# arduino-double.net
KiCad netlist of a schematic drawn in EAGLE
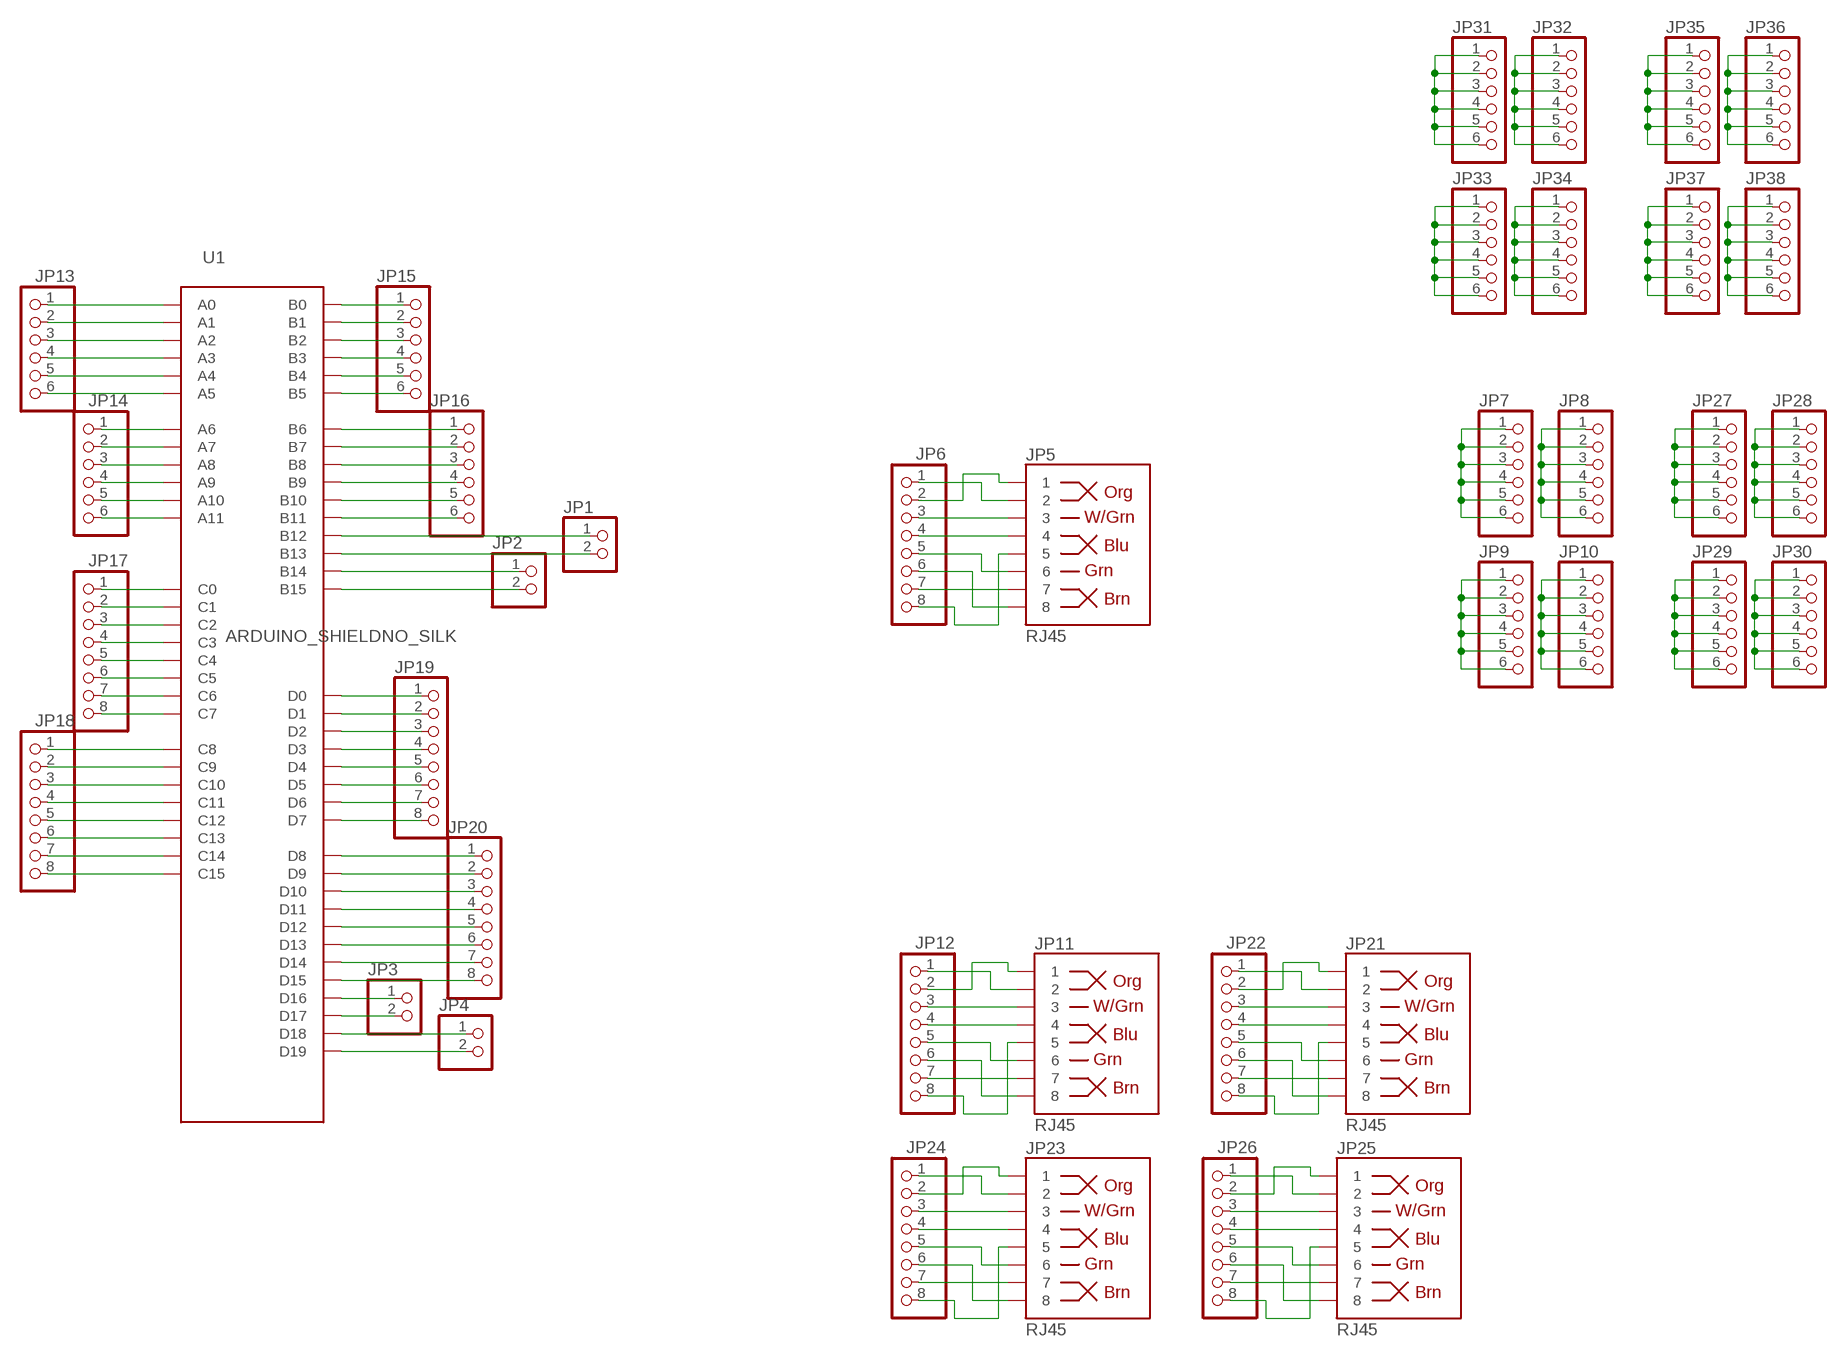
[diagram p0: schematic, sheet 1]

(export (version "E")
  (design (tool "Eeschema 10.0.6"))
  (components
    (comp (ref "JP1")
      (value "PINHD-1X2")
      (footprint "eagle-import:1X02")
      (libsource (lib "eagle-import") (part "PINHD-1X2"))
    )
    (comp (ref "JP2")
      (value "PINHD-1X2")
      (footprint "eagle-import:1X02")
      (libsource (lib "eagle-import") (part "PINHD-1X2"))
    )
    (comp (ref "JP3")
      (value "PINHD-1X2")
      (footprint "eagle-import:1X02")
      (libsource (lib "eagle-import") (part "PINHD-1X2"))
    )
    (comp (ref "JP4")
      (value "PINHD-1X2")
      (footprint "eagle-import:1X02")
      (libsource (lib "eagle-import") (part "PINHD-1X2"))
    )
    (comp (ref "JP5")
      (value "RJ45")
      (footprint "eagle-import:RJ45-8")
      (libsource (lib "eagle-import") (part "RJ45-8PTH"))
    )
    (comp (ref "JP6")
      (value "PINHD-1X8")
      (footprint "eagle-import:1X08")
      (libsource (lib "eagle-import") (part "PINHD-1X8"))
    )
    (comp (ref "JP7")
      (value "PINHD-1X6")
      (footprint "eagle-import:1X06")
      (libsource (lib "eagle-import") (part "PINHD-1X6"))
    )
    (comp (ref "JP8")
      (value "PINHD-1X6")
      (footprint "eagle-import:1X06")
      (libsource (lib "eagle-import") (part "PINHD-1X6"))
    )
    (comp (ref "JP9")
      (value "PINHD-1X6")
      (footprint "eagle-import:1X06")
      (libsource (lib "eagle-import") (part "PINHD-1X6"))
    )
    (comp (ref "JP10")
      (value "PINHD-1X6")
      (footprint "eagle-import:1X06")
      (libsource (lib "eagle-import") (part "PINHD-1X6"))
    )
    (comp (ref "JP11")
      (value "RJ45")
      (footprint "eagle-import:RJ45-8")
      (libsource (lib "eagle-import") (part "RJ45-8PTH"))
    )
    (comp (ref "JP12")
      (value "PINHD-1X8")
      (footprint "eagle-import:1X08")
      (libsource (lib "eagle-import") (part "PINHD-1X8"))
    )
    (comp (ref "JP13")
      (value "PINHD-1X6")
      (footprint "eagle-import:1X06")
      (libsource (lib "eagle-import") (part "PINHD-1X6"))
    )
    (comp (ref "JP14")
      (value "PINHD-1X6")
      (footprint "eagle-import:1X06")
      (libsource (lib "eagle-import") (part "PINHD-1X6"))
    )
    (comp (ref "JP15")
      (value "PINHD-1X6")
      (footprint "eagle-import:1X06")
      (libsource (lib "eagle-import") (part "PINHD-1X6"))
    )
    (comp (ref "JP16")
      (value "PINHD-1X6")
      (footprint "eagle-import:1X06")
      (libsource (lib "eagle-import") (part "PINHD-1X6"))
    )
    (comp (ref "JP17")
      (value "PINHD-1X8")
      (footprint "eagle-import:1X08")
      (libsource (lib "eagle-import") (part "PINHD-1X8"))
    )
    (comp (ref "JP18")
      (value "PINHD-1X8")
      (footprint "eagle-import:1X08")
      (libsource (lib "eagle-import") (part "PINHD-1X8"))
    )
    (comp (ref "JP19")
      (value "PINHD-1X8")
      (footprint "eagle-import:1X08")
      (libsource (lib "eagle-import") (part "PINHD-1X8"))
    )
    (comp (ref "JP20")
      (value "PINHD-1X8")
      (footprint "eagle-import:1X08")
      (libsource (lib "eagle-import") (part "PINHD-1X8"))
    )
    (comp (ref "JP21")
      (value "RJ45")
      (footprint "eagle-import:RJ45-8")
      (libsource (lib "eagle-import") (part "RJ45-8PTH"))
    )
    (comp (ref "JP22")
      (value "PINHD-1X8")
      (footprint "eagle-import:1X08")
      (libsource (lib "eagle-import") (part "PINHD-1X8"))
    )
    (comp (ref "JP23")
      (value "RJ45")
      (footprint "eagle-import:RJ45-8")
      (libsource (lib "eagle-import") (part "RJ45-8PTH"))
    )
    (comp (ref "JP24")
      (value "PINHD-1X8")
      (footprint "eagle-import:1X08")
      (libsource (lib "eagle-import") (part "PINHD-1X8"))
    )
    (comp (ref "JP25")
      (value "RJ45")
      (footprint "eagle-import:RJ45-8")
      (libsource (lib "eagle-import") (part "RJ45-8PTH"))
    )
    (comp (ref "JP26")
      (value "PINHD-1X8")
      (footprint "eagle-import:1X08")
      (libsource (lib "eagle-import") (part "PINHD-1X8"))
    )
    (comp (ref "JP27")
      (value "PINHD-1X6")
      (footprint "eagle-import:1X06")
      (libsource (lib "eagle-import") (part "PINHD-1X6"))
    )
    (comp (ref "JP28")
      (value "PINHD-1X6")
      (footprint "eagle-import:1X06")
      (libsource (lib "eagle-import") (part "PINHD-1X6"))
    )
    (comp (ref "JP29")
      (value "PINHD-1X6")
      (footprint "eagle-import:1X06")
      (libsource (lib "eagle-import") (part "PINHD-1X6"))
    )
    (comp (ref "JP30")
      (value "PINHD-1X6")
      (footprint "eagle-import:1X06")
      (libsource (lib "eagle-import") (part "PINHD-1X6"))
    )
    (comp (ref "JP31")
      (value "PINHD-1X6")
      (footprint "eagle-import:1X06")
      (libsource (lib "eagle-import") (part "PINHD-1X6"))
    )
    (comp (ref "JP32")
      (value "PINHD-1X6")
      (footprint "eagle-import:1X06")
      (libsource (lib "eagle-import") (part "PINHD-1X6"))
    )
    (comp (ref "JP33")
      (value "PINHD-1X6")
      (footprint "eagle-import:1X06")
      (libsource (lib "eagle-import") (part "PINHD-1X6"))
    )
    (comp (ref "JP34")
      (value "PINHD-1X6")
      (footprint "eagle-import:1X06")
      (libsource (lib "eagle-import") (part "PINHD-1X6"))
    )
    (comp (ref "JP35")
      (value "PINHD-1X6")
      (footprint "eagle-import:1X06")
      (libsource (lib "eagle-import") (part "PINHD-1X6"))
    )
    (comp (ref "JP36")
      (value "PINHD-1X6")
      (footprint "eagle-import:1X06")
      (libsource (lib "eagle-import") (part "PINHD-1X6"))
    )
    (comp (ref "JP37")
      (value "PINHD-1X6")
      (footprint "eagle-import:1X06")
      (libsource (lib "eagle-import") (part "PINHD-1X6"))
    )
    (comp (ref "JP38")
      (value "PINHD-1X6")
      (footprint "eagle-import:1X06")
      (libsource (lib "eagle-import") (part "PINHD-1X6"))
    )
    (comp (ref "U1")
      (value "ARDUINO_SHIELDNO_SILK")
      (footprint "eagle-import:DUEMILANOVE_VIAS")
      (libsource (lib "eagle-import") (part "ARDUINO_SHIELDNO_SILK"))
    )
  )
  (nets
    (net (code "1") (name "Net-(JP1-Pad1)") (class "Default")
      (node (ref "JP1") (pin "1") (pinfunction "1_1") (pintype "passive"))
      (node (ref "U1") (pin "B12") (pinfunction "B12_B12") (pintype "bidirectional"))
    )
    (net (code "2") (name "Net-(JP1-Pad2)") (class "Default")
      (node (ref "JP1") (pin "2") (pinfunction "2_2") (pintype "passive"))
      (node (ref "U1") (pin "B13") (pinfunction "B13_B13") (pintype "bidirectional"))
    )
    (net (code "3") (name "Net-(JP2-Pad1)") (class "Default")
      (node (ref "JP2") (pin "1") (pinfunction "1_1") (pintype "passive"))
      (node (ref "U1") (pin "B14") (pinfunction "B14_B14") (pintype "bidirectional"))
    )
    (net (code "4") (name "Net-(JP2-Pad2)") (class "Default")
      (node (ref "JP2") (pin "2") (pinfunction "2_2") (pintype "passive"))
      (node (ref "U1") (pin "B15") (pinfunction "B15_B15") (pintype "bidirectional"))
    )
    (net (code "5") (name "Net-(JP3-Pad1)") (class "Default")
      (node (ref "JP3") (pin "1") (pinfunction "1_1") (pintype "passive"))
      (node (ref "U1") (pin "D16") (pinfunction "D16_D16") (pintype "bidirectional"))
    )
    (net (code "6") (name "Net-(JP3-Pad2)") (class "Default")
      (node (ref "JP3") (pin "2") (pinfunction "2_2") (pintype "passive"))
      (node (ref "U1") (pin "D17") (pinfunction "D17_D17") (pintype "bidirectional"))
    )
    (net (code "7") (name "Net-(JP4-Pad1)") (class "Default")
      (node (ref "JP4") (pin "1") (pinfunction "1_1") (pintype "passive"))
      (node (ref "U1") (pin "D18") (pinfunction "D18_D18") (pintype "bidirectional"))
    )
    (net (code "8") (name "Net-(JP4-Pad2)") (class "Default")
      (node (ref "JP4") (pin "2") (pinfunction "2_2") (pintype "passive"))
      (node (ref "U1") (pin "D19") (pinfunction "D19_D19") (pintype "bidirectional"))
    )
    (net (code "9") (name "Net-(JP5-Pad1)") (class "Default")
      (node (ref "JP5") (pin "1") (pinfunction "1_1") (pintype "bidirectional"))
      (node (ref "JP6") (pin "2") (pinfunction "2_2") (pintype "passive"))
    )
    (net (code "10") (name "Net-(JP5-Pad2)") (class "Default")
      (node (ref "JP5") (pin "2") (pinfunction "2_2") (pintype "bidirectional"))
      (node (ref "JP6") (pin "1") (pinfunction "1_1") (pintype "passive"))
    )
    (net (code "11") (name "Net-(JP5-Pad3)") (class "Default")
      (node (ref "JP5") (pin "3") (pinfunction "3_3") (pintype "bidirectional"))
      (node (ref "JP6") (pin "3") (pinfunction "3_3") (pintype "passive"))
    )
    (net (code "12") (name "Net-(JP5-Pad4)") (class "Default")
      (node (ref "JP5") (pin "4") (pinfunction "4_4") (pintype "bidirectional"))
      (node (ref "JP6") (pin "4") (pinfunction "4_4") (pintype "passive"))
    )
    (net (code "13") (name "Net-(JP5-Pad5)") (class "Default")
      (node (ref "JP5") (pin "5") (pinfunction "5_5") (pintype "bidirectional"))
      (node (ref "JP6") (pin "8") (pinfunction "8_8") (pintype "passive"))
    )
    (net (code "14") (name "Net-(JP5-Pad6)") (class "Default")
      (node (ref "JP5") (pin "6") (pinfunction "6_6") (pintype "bidirectional"))
      (node (ref "JP6") (pin "5") (pinfunction "5_5") (pintype "passive"))
    )
    (net (code "15") (name "Net-(JP5-Pad7)") (class "Default")
      (node (ref "JP5") (pin "7") (pinfunction "7_7") (pintype "bidirectional"))
      (node (ref "JP6") (pin "7") (pinfunction "7_7") (pintype "passive"))
    )
    (net (code "16") (name "Net-(JP5-Pad8)") (class "Default")
      (node (ref "JP5") (pin "8") (pinfunction "8_8") (pintype "bidirectional"))
      (node (ref "JP6") (pin "6") (pinfunction "6_6") (pintype "passive"))
    )
    (net (code "17") (name "Net-(JP7-Pad1)") (class "Default")
      (node (ref "JP7") (pin "1") (pinfunction "1_1") (pintype "passive"))
      (node (ref "JP7") (pin "2") (pinfunction "2_2") (pintype "passive"))
      (node (ref "JP7") (pin "3") (pinfunction "3_3") (pintype "passive"))
      (node (ref "JP7") (pin "4") (pinfunction "4_4") (pintype "passive"))
      (node (ref "JP7") (pin "5") (pinfunction "5_5") (pintype "passive"))
      (node (ref "JP7") (pin "6") (pinfunction "6_6") (pintype "passive"))
    )
    (net (code "18") (name "Net-(JP8-Pad1)") (class "Default")
      (node (ref "JP8") (pin "1") (pinfunction "1_1") (pintype "passive"))
      (node (ref "JP8") (pin "2") (pinfunction "2_2") (pintype "passive"))
      (node (ref "JP8") (pin "3") (pinfunction "3_3") (pintype "passive"))
      (node (ref "JP8") (pin "4") (pinfunction "4_4") (pintype "passive"))
      (node (ref "JP8") (pin "5") (pinfunction "5_5") (pintype "passive"))
      (node (ref "JP8") (pin "6") (pinfunction "6_6") (pintype "passive"))
    )
    (net (code "19") (name "Net-(JP9-Pad1)") (class "Default")
      (node (ref "JP9") (pin "1") (pinfunction "1_1") (pintype "passive"))
      (node (ref "JP9") (pin "2") (pinfunction "2_2") (pintype "passive"))
      (node (ref "JP9") (pin "3") (pinfunction "3_3") (pintype "passive"))
      (node (ref "JP9") (pin "4") (pinfunction "4_4") (pintype "passive"))
      (node (ref "JP9") (pin "5") (pinfunction "5_5") (pintype "passive"))
      (node (ref "JP9") (pin "6") (pinfunction "6_6") (pintype "passive"))
    )
    (net (code "20") (name "Net-(JP10-Pad1)") (class "Default")
      (node (ref "JP10") (pin "1") (pinfunction "1_1") (pintype "passive"))
      (node (ref "JP10") (pin "2") (pinfunction "2_2") (pintype "passive"))
      (node (ref "JP10") (pin "3") (pinfunction "3_3") (pintype "passive"))
      (node (ref "JP10") (pin "4") (pinfunction "4_4") (pintype "passive"))
      (node (ref "JP10") (pin "5") (pinfunction "5_5") (pintype "passive"))
      (node (ref "JP10") (pin "6") (pinfunction "6_6") (pintype "passive"))
    )
    (net (code "21") (name "Net-(JP11-Pad1)") (class "Default")
      (node (ref "JP11") (pin "1") (pinfunction "1_1") (pintype "bidirectional"))
      (node (ref "JP12") (pin "2") (pinfunction "2_2") (pintype "passive"))
    )
    (net (code "22") (name "Net-(JP11-Pad2)") (class "Default")
      (node (ref "JP11") (pin "2") (pinfunction "2_2") (pintype "bidirectional"))
      (node (ref "JP12") (pin "1") (pinfunction "1_1") (pintype "passive"))
    )
    (net (code "23") (name "Net-(JP11-Pad3)") (class "Default")
      (node (ref "JP11") (pin "3") (pinfunction "3_3") (pintype "bidirectional"))
      (node (ref "JP12") (pin "3") (pinfunction "3_3") (pintype "passive"))
    )
    (net (code "24") (name "Net-(JP11-Pad4)") (class "Default")
      (node (ref "JP11") (pin "4") (pinfunction "4_4") (pintype "bidirectional"))
      (node (ref "JP12") (pin "4") (pinfunction "4_4") (pintype "passive"))
    )
    (net (code "25") (name "Net-(JP11-Pad5)") (class "Default")
      (node (ref "JP11") (pin "5") (pinfunction "5_5") (pintype "bidirectional"))
      (node (ref "JP12") (pin "8") (pinfunction "8_8") (pintype "passive"))
    )
    (net (code "26") (name "Net-(JP11-Pad6)") (class "Default")
      (node (ref "JP11") (pin "6") (pinfunction "6_6") (pintype "bidirectional"))
      (node (ref "JP12") (pin "5") (pinfunction "5_5") (pintype "passive"))
    )
    (net (code "27") (name "Net-(JP11-Pad7)") (class "Default")
      (node (ref "JP11") (pin "7") (pinfunction "7_7") (pintype "bidirectional"))
      (node (ref "JP12") (pin "7") (pinfunction "7_7") (pintype "passive"))
    )
    (net (code "28") (name "Net-(JP11-Pad8)") (class "Default")
      (node (ref "JP11") (pin "8") (pinfunction "8_8") (pintype "bidirectional"))
      (node (ref "JP12") (pin "6") (pinfunction "6_6") (pintype "passive"))
    )
    (net (code "29") (name "Net-(JP13-Pad1)") (class "Default")
      (node (ref "JP13") (pin "1") (pinfunction "1_1") (pintype "passive"))
      (node (ref "U1") (pin "A0") (pinfunction "A0_A0") (pintype "bidirectional"))
    )
    (net (code "30") (name "Net-(JP13-Pad2)") (class "Default")
      (node (ref "JP13") (pin "2") (pinfunction "2_2") (pintype "passive"))
      (node (ref "U1") (pin "A1") (pinfunction "A1_A1") (pintype "bidirectional"))
    )
    (net (code "31") (name "Net-(JP13-Pad3)") (class "Default")
      (node (ref "JP13") (pin "3") (pinfunction "3_3") (pintype "passive"))
      (node (ref "U1") (pin "A2") (pinfunction "A2_A2") (pintype "bidirectional"))
    )
    (net (code "32") (name "Net-(JP13-Pad4)") (class "Default")
      (node (ref "JP13") (pin "4") (pinfunction "4_4") (pintype "passive"))
      (node (ref "U1") (pin "A3") (pinfunction "A3_A3") (pintype "bidirectional"))
    )
    (net (code "33") (name "Net-(JP13-Pad5)") (class "Default")
      (node (ref "JP13") (pin "5") (pinfunction "5_5") (pintype "passive"))
      (node (ref "U1") (pin "A4") (pinfunction "A4_A4") (pintype "bidirectional"))
    )
    (net (code "34") (name "Net-(JP13-Pad6)") (class "Default")
      (node (ref "JP13") (pin "6") (pinfunction "6_6") (pintype "passive"))
      (node (ref "U1") (pin "A5") (pinfunction "A5_A5") (pintype "bidirectional"))
    )
    (net (code "35") (name "Net-(JP14-Pad1)") (class "Default")
      (node (ref "JP14") (pin "1") (pinfunction "1_1") (pintype "passive"))
      (node (ref "U1") (pin "A6") (pinfunction "A6_A6") (pintype "bidirectional"))
    )
    (net (code "36") (name "Net-(JP14-Pad2)") (class "Default")
      (node (ref "JP14") (pin "2") (pinfunction "2_2") (pintype "passive"))
      (node (ref "U1") (pin "A7") (pinfunction "A7_A7") (pintype "bidirectional"))
    )
    (net (code "37") (name "Net-(JP14-Pad3)") (class "Default")
      (node (ref "JP14") (pin "3") (pinfunction "3_3") (pintype "passive"))
      (node (ref "U1") (pin "A8") (pinfunction "A8_A8") (pintype "bidirectional"))
    )
    (net (code "38") (name "Net-(JP14-Pad4)") (class "Default")
      (node (ref "JP14") (pin "4") (pinfunction "4_4") (pintype "passive"))
      (node (ref "U1") (pin "A9") (pinfunction "A9_A9") (pintype "bidirectional"))
    )
    (net (code "39") (name "Net-(JP14-Pad5)") (class "Default")
      (node (ref "JP14") (pin "5") (pinfunction "5_5") (pintype "passive"))
      (node (ref "U1") (pin "A10") (pinfunction "A10_A10") (pintype "bidirectional"))
    )
    (net (code "40") (name "Net-(JP14-Pad6)") (class "Default")
      (node (ref "JP14") (pin "6") (pinfunction "6_6") (pintype "passive"))
      (node (ref "U1") (pin "A11") (pinfunction "A11_A11") (pintype "bidirectional"))
    )
    (net (code "41") (name "Net-(JP15-Pad1)") (class "Default")
      (node (ref "JP15") (pin "1") (pinfunction "1_1") (pintype "passive"))
      (node (ref "U1") (pin "B0") (pinfunction "B0_B0") (pintype "bidirectional"))
    )
    (net (code "42") (name "Net-(JP15-Pad2)") (class "Default")
      (node (ref "JP15") (pin "2") (pinfunction "2_2") (pintype "passive"))
      (node (ref "U1") (pin "B1") (pinfunction "B1_B1") (pintype "bidirectional"))
    )
    (net (code "43") (name "Net-(JP15-Pad3)") (class "Default")
      (node (ref "JP15") (pin "3") (pinfunction "3_3") (pintype "passive"))
      (node (ref "U1") (pin "B2") (pinfunction "B2_B2") (pintype "bidirectional"))
    )
    (net (code "44") (name "Net-(JP15-Pad4)") (class "Default")
      (node (ref "JP15") (pin "4") (pinfunction "4_4") (pintype "passive"))
      (node (ref "U1") (pin "B3") (pinfunction "B3_B3") (pintype "bidirectional"))
    )
    (net (code "45") (name "Net-(JP15-Pad5)") (class "Default")
      (node (ref "JP15") (pin "5") (pinfunction "5_5") (pintype "passive"))
      (node (ref "U1") (pin "B4") (pinfunction "B4_B4") (pintype "bidirectional"))
    )
    (net (code "46") (name "Net-(JP15-Pad6)") (class "Default")
      (node (ref "JP15") (pin "6") (pinfunction "6_6") (pintype "passive"))
      (node (ref "U1") (pin "B5") (pinfunction "B5_B5") (pintype "bidirectional"))
    )
    (net (code "47") (name "Net-(JP16-Pad1)") (class "Default")
      (node (ref "JP16") (pin "1") (pinfunction "1_1") (pintype "passive"))
      (node (ref "U1") (pin "B6") (pinfunction "B6_B6") (pintype "bidirectional"))
    )
    (net (code "48") (name "Net-(JP16-Pad2)") (class "Default")
      (node (ref "JP16") (pin "2") (pinfunction "2_2") (pintype "passive"))
      (node (ref "U1") (pin "B7") (pinfunction "B7_B7") (pintype "bidirectional"))
    )
    (net (code "49") (name "Net-(JP16-Pad3)") (class "Default")
      (node (ref "JP16") (pin "3") (pinfunction "3_3") (pintype "passive"))
      (node (ref "U1") (pin "B8") (pinfunction "B8_B8") (pintype "bidirectional"))
    )
    (net (code "50") (name "Net-(JP16-Pad4)") (class "Default")
      (node (ref "JP16") (pin "4") (pinfunction "4_4") (pintype "passive"))
      (node (ref "U1") (pin "B9") (pinfunction "B9_B9") (pintype "bidirectional"))
    )
    (net (code "51") (name "Net-(JP16-Pad5)") (class "Default")
      (node (ref "JP16") (pin "5") (pinfunction "5_5") (pintype "passive"))
      (node (ref "U1") (pin "B10") (pinfunction "B10_B10") (pintype "bidirectional"))
    )
    (net (code "52") (name "Net-(JP16-Pad6)") (class "Default")
      (node (ref "JP16") (pin "6") (pinfunction "6_6") (pintype "passive"))
      (node (ref "U1") (pin "B11") (pinfunction "B11_B11") (pintype "bidirectional"))
    )
    (net (code "53") (name "Net-(JP17-Pad1)") (class "Default")
      (node (ref "JP17") (pin "1") (pinfunction "1_1") (pintype "passive"))
      (node (ref "U1") (pin "C0") (pinfunction "C0_C0") (pintype "bidirectional"))
    )
    (net (code "54") (name "Net-(JP17-Pad2)") (class "Default")
      (node (ref "JP17") (pin "2") (pinfunction "2_2") (pintype "passive"))
      (node (ref "U1") (pin "C1") (pinfunction "C1_C1") (pintype "bidirectional"))
    )
    (net (code "55") (name "Net-(JP17-Pad3)") (class "Default")
      (node (ref "JP17") (pin "3") (pinfunction "3_3") (pintype "passive"))
      (node (ref "U1") (pin "C2") (pinfunction "C2_C2") (pintype "bidirectional"))
    )
    (net (code "56") (name "Net-(JP17-Pad4)") (class "Default")
      (node (ref "JP17") (pin "4") (pinfunction "4_4") (pintype "passive"))
      (node (ref "U1") (pin "C3") (pinfunction "C3_C3") (pintype "bidirectional"))
    )
    (net (code "57") (name "Net-(JP17-Pad5)") (class "Default")
      (node (ref "JP17") (pin "5") (pinfunction "5_5") (pintype "passive"))
      (node (ref "U1") (pin "C4") (pinfunction "C4_C4") (pintype "bidirectional"))
    )
    (net (code "58") (name "Net-(JP17-Pad6)") (class "Default")
      (node (ref "JP17") (pin "6") (pinfunction "6_6") (pintype "passive"))
      (node (ref "U1") (pin "C5") (pinfunction "C5_C5") (pintype "bidirectional"))
    )
    (net (code "59") (name "Net-(JP17-Pad7)") (class "Default")
      (node (ref "JP17") (pin "7") (pinfunction "7_7") (pintype "passive"))
      (node (ref "U1") (pin "C6") (pinfunction "C6_C6") (pintype "bidirectional"))
    )
    (net (code "60") (name "Net-(JP17-Pad8)") (class "Default")
      (node (ref "JP17") (pin "8") (pinfunction "8_8") (pintype "passive"))
      (node (ref "U1") (pin "C7") (pinfunction "C7_C7") (pintype "bidirectional"))
    )
    (net (code "61") (name "Net-(JP18-Pad1)") (class "Default")
      (node (ref "JP18") (pin "1") (pinfunction "1_1") (pintype "passive"))
      (node (ref "U1") (pin "C8") (pinfunction "C8_C8") (pintype "bidirectional"))
    )
    (net (code "62") (name "Net-(JP18-Pad2)") (class "Default")
      (node (ref "JP18") (pin "2") (pinfunction "2_2") (pintype "passive"))
      (node (ref "U1") (pin "C9") (pinfunction "C9_C9") (pintype "bidirectional"))
    )
    (net (code "63") (name "Net-(JP18-Pad3)") (class "Default")
      (node (ref "JP18") (pin "3") (pinfunction "3_3") (pintype "passive"))
      (node (ref "U1") (pin "C10") (pinfunction "C10_C10") (pintype "bidirectional"))
    )
    (net (code "64") (name "Net-(JP18-Pad4)") (class "Default")
      (node (ref "JP18") (pin "4") (pinfunction "4_4") (pintype "passive"))
      (node (ref "U1") (pin "C11") (pinfunction "C11_C11") (pintype "bidirectional"))
    )
    (net (code "65") (name "Net-(JP18-Pad5)") (class "Default")
      (node (ref "JP18") (pin "5") (pinfunction "5_5") (pintype "passive"))
      (node (ref "U1") (pin "C12") (pinfunction "C12_C12") (pintype "bidirectional"))
    )
    (net (code "66") (name "Net-(JP18-Pad6)") (class "Default")
      (node (ref "JP18") (pin "6") (pinfunction "6_6") (pintype "passive"))
      (node (ref "U1") (pin "C13") (pinfunction "C13_C13") (pintype "bidirectional"))
    )
    (net (code "67") (name "Net-(JP18-Pad7)") (class "Default")
      (node (ref "JP18") (pin "7") (pinfunction "7_7") (pintype "passive"))
      (node (ref "U1") (pin "C14") (pinfunction "C14_C14") (pintype "bidirectional"))
    )
    (net (code "68") (name "Net-(JP18-Pad8)") (class "Default")
      (node (ref "JP18") (pin "8") (pinfunction "8_8") (pintype "passive"))
      (node (ref "U1") (pin "C15") (pinfunction "C15_C15") (pintype "bidirectional"))
    )
    (net (code "69") (name "Net-(JP19-Pad1)") (class "Default")
      (node (ref "JP19") (pin "1") (pinfunction "1_1") (pintype "passive"))
      (node (ref "U1") (pin "D0") (pinfunction "D0_D0") (pintype "bidirectional"))
    )
    (net (code "70") (name "Net-(JP19-Pad2)") (class "Default")
      (node (ref "JP19") (pin "2") (pinfunction "2_2") (pintype "passive"))
      (node (ref "U1") (pin "D1") (pinfunction "D1_D1") (pintype "bidirectional"))
    )
    (net (code "71") (name "Net-(JP19-Pad3)") (class "Default")
      (node (ref "JP19") (pin "3") (pinfunction "3_3") (pintype "passive"))
      (node (ref "U1") (pin "D2") (pinfunction "D2_D2") (pintype "bidirectional"))
    )
    (net (code "72") (name "Net-(JP19-Pad4)") (class "Default")
      (node (ref "JP19") (pin "4") (pinfunction "4_4") (pintype "passive"))
      (node (ref "U1") (pin "D3") (pinfunction "D3_D3") (pintype "bidirectional"))
    )
    (net (code "73") (name "Net-(JP19-Pad5)") (class "Default")
      (node (ref "JP19") (pin "5") (pinfunction "5_5") (pintype "passive"))
      (node (ref "U1") (pin "D4") (pinfunction "D4_D4") (pintype "bidirectional"))
    )
    (net (code "74") (name "Net-(JP19-Pad6)") (class "Default")
      (node (ref "JP19") (pin "6") (pinfunction "6_6") (pintype "passive"))
      (node (ref "U1") (pin "D5") (pinfunction "D5_D5") (pintype "bidirectional"))
    )
    (net (code "75") (name "Net-(JP19-Pad7)") (class "Default")
      (node (ref "JP19") (pin "7") (pinfunction "7_7") (pintype "passive"))
      (node (ref "U1") (pin "D6") (pinfunction "D6_D6") (pintype "bidirectional"))
    )
    (net (code "76") (name "Net-(JP19-Pad8)") (class "Default")
      (node (ref "JP19") (pin "8") (pinfunction "8_8") (pintype "passive"))
      (node (ref "U1") (pin "D7") (pinfunction "D7_D7") (pintype "bidirectional"))
    )
    (net (code "77") (name "Net-(JP20-Pad1)") (class "Default")
      (node (ref "JP20") (pin "1") (pinfunction "1_1") (pintype "passive"))
      (node (ref "U1") (pin "D8") (pinfunction "D8_D8") (pintype "bidirectional"))
    )
    (net (code "78") (name "Net-(JP20-Pad2)") (class "Default")
      (node (ref "JP20") (pin "2") (pinfunction "2_2") (pintype "passive"))
      (node (ref "U1") (pin "D9") (pinfunction "D9_D9") (pintype "bidirectional"))
    )
    (net (code "79") (name "Net-(JP20-Pad3)") (class "Default")
      (node (ref "JP20") (pin "3") (pinfunction "3_3") (pintype "passive"))
      (node (ref "U1") (pin "D10") (pinfunction "D10_D10") (pintype "bidirectional"))
    )
    (net (code "80") (name "Net-(JP20-Pad4)") (class "Default")
      (node (ref "JP20") (pin "4") (pinfunction "4_4") (pintype "passive"))
      (node (ref "U1") (pin "D11") (pinfunction "D11_D11") (pintype "bidirectional"))
    )
    (net (code "81") (name "Net-(JP20-Pad5)") (class "Default")
      (node (ref "JP20") (pin "5") (pinfunction "5_5") (pintype "passive"))
      (node (ref "U1") (pin "D12") (pinfunction "D12_D12") (pintype "bidirectional"))
    )
    (net (code "82") (name "Net-(JP20-Pad6)") (class "Default")
      (node (ref "JP20") (pin "6") (pinfunction "6_6") (pintype "passive"))
      (node (ref "U1") (pin "D13") (pinfunction "D13_D13") (pintype "bidirectional"))
    )
    (net (code "83") (name "Net-(JP20-Pad7)") (class "Default")
      (node (ref "JP20") (pin "7") (pinfunction "7_7") (pintype "passive"))
      (node (ref "U1") (pin "D14") (pinfunction "D14_D14") (pintype "bidirectional"))
    )
    (net (code "84") (name "Net-(JP20-Pad8)") (class "Default")
      (node (ref "JP20") (pin "8") (pinfunction "8_8") (pintype "passive"))
      (node (ref "U1") (pin "D15") (pinfunction "D15_D15") (pintype "bidirectional"))
    )
    (net (code "85") (name "Net-(JP21-Pad1)") (class "Default")
      (node (ref "JP21") (pin "1") (pinfunction "1_1") (pintype "bidirectional"))
      (node (ref "JP22") (pin "2") (pinfunction "2_2") (pintype "passive"))
    )
    (net (code "86") (name "Net-(JP21-Pad2)") (class "Default")
      (node (ref "JP21") (pin "2") (pinfunction "2_2") (pintype "bidirectional"))
      (node (ref "JP22") (pin "1") (pinfunction "1_1") (pintype "passive"))
    )
    (net (code "87") (name "Net-(JP21-Pad3)") (class "Default")
      (node (ref "JP21") (pin "3") (pinfunction "3_3") (pintype "bidirectional"))
      (node (ref "JP22") (pin "3") (pinfunction "3_3") (pintype "passive"))
    )
    (net (code "88") (name "Net-(JP21-Pad4)") (class "Default")
      (node (ref "JP21") (pin "4") (pinfunction "4_4") (pintype "bidirectional"))
      (node (ref "JP22") (pin "4") (pinfunction "4_4") (pintype "passive"))
    )
    (net (code "89") (name "Net-(JP21-Pad5)") (class "Default")
      (node (ref "JP21") (pin "5") (pinfunction "5_5") (pintype "bidirectional"))
      (node (ref "JP22") (pin "8") (pinfunction "8_8") (pintype "passive"))
    )
    (net (code "90") (name "Net-(JP21-Pad6)") (class "Default")
      (node (ref "JP21") (pin "6") (pinfunction "6_6") (pintype "bidirectional"))
      (node (ref "JP22") (pin "5") (pinfunction "5_5") (pintype "passive"))
    )
    (net (code "91") (name "Net-(JP21-Pad7)") (class "Default")
      (node (ref "JP21") (pin "7") (pinfunction "7_7") (pintype "bidirectional"))
      (node (ref "JP22") (pin "7") (pinfunction "7_7") (pintype "passive"))
    )
    (net (code "92") (name "Net-(JP21-Pad8)") (class "Default")
      (node (ref "JP21") (pin "8") (pinfunction "8_8") (pintype "bidirectional"))
      (node (ref "JP22") (pin "6") (pinfunction "6_6") (pintype "passive"))
    )
    (net (code "93") (name "Net-(JP23-Pad1)") (class "Default")
      (node (ref "JP23") (pin "1") (pinfunction "1_1") (pintype "bidirectional"))
      (node (ref "JP24") (pin "2") (pinfunction "2_2") (pintype "passive"))
    )
    (net (code "94") (name "Net-(JP23-Pad2)") (class "Default")
      (node (ref "JP23") (pin "2") (pinfunction "2_2") (pintype "bidirectional"))
      (node (ref "JP24") (pin "1") (pinfunction "1_1") (pintype "passive"))
    )
    (net (code "95") (name "Net-(JP23-Pad3)") (class "Default")
      (node (ref "JP23") (pin "3") (pinfunction "3_3") (pintype "bidirectional"))
      (node (ref "JP24") (pin "3") (pinfunction "3_3") (pintype "passive"))
    )
    (net (code "96") (name "Net-(JP23-Pad4)") (class "Default")
      (node (ref "JP23") (pin "4") (pinfunction "4_4") (pintype "bidirectional"))
      (node (ref "JP24") (pin "4") (pinfunction "4_4") (pintype "passive"))
    )
    (net (code "97") (name "Net-(JP23-Pad5)") (class "Default")
      (node (ref "JP23") (pin "5") (pinfunction "5_5") (pintype "bidirectional"))
      (node (ref "JP24") (pin "8") (pinfunction "8_8") (pintype "passive"))
    )
    (net (code "98") (name "Net-(JP23-Pad6)") (class "Default")
      (node (ref "JP23") (pin "6") (pinfunction "6_6") (pintype "bidirectional"))
      (node (ref "JP24") (pin "5") (pinfunction "5_5") (pintype "passive"))
    )
    (net (code "99") (name "Net-(JP23-Pad7)") (class "Default")
      (node (ref "JP23") (pin "7") (pinfunction "7_7") (pintype "bidirectional"))
      (node (ref "JP24") (pin "7") (pinfunction "7_7") (pintype "passive"))
    )
    (net (code "100") (name "Net-(JP23-Pad8)") (class "Default")
      (node (ref "JP23") (pin "8") (pinfunction "8_8") (pintype "bidirectional"))
      (node (ref "JP24") (pin "6") (pinfunction "6_6") (pintype "passive"))
    )
    (net (code "101") (name "Net-(JP25-Pad1)") (class "Default")
      (node (ref "JP25") (pin "1") (pinfunction "1_1") (pintype "bidirectional"))
      (node (ref "JP26") (pin "2") (pinfunction "2_2") (pintype "passive"))
    )
    (net (code "102") (name "Net-(JP25-Pad2)") (class "Default")
      (node (ref "JP25") (pin "2") (pinfunction "2_2") (pintype "bidirectional"))
      (node (ref "JP26") (pin "1") (pinfunction "1_1") (pintype "passive"))
    )
    (net (code "103") (name "Net-(JP25-Pad3)") (class "Default")
      (node (ref "JP25") (pin "3") (pinfunction "3_3") (pintype "bidirectional"))
      (node (ref "JP26") (pin "3") (pinfunction "3_3") (pintype "passive"))
    )
    (net (code "104") (name "Net-(JP25-Pad4)") (class "Default")
      (node (ref "JP25") (pin "4") (pinfunction "4_4") (pintype "bidirectional"))
      (node (ref "JP26") (pin "4") (pinfunction "4_4") (pintype "passive"))
    )
    (net (code "105") (name "Net-(JP25-Pad5)") (class "Default")
      (node (ref "JP25") (pin "5") (pinfunction "5_5") (pintype "bidirectional"))
      (node (ref "JP26") (pin "8") (pinfunction "8_8") (pintype "passive"))
    )
    (net (code "106") (name "Net-(JP25-Pad6)") (class "Default")
      (node (ref "JP25") (pin "6") (pinfunction "6_6") (pintype "bidirectional"))
      (node (ref "JP26") (pin "5") (pinfunction "5_5") (pintype "passive"))
    )
    (net (code "107") (name "Net-(JP25-Pad7)") (class "Default")
      (node (ref "JP25") (pin "7") (pinfunction "7_7") (pintype "bidirectional"))
      (node (ref "JP26") (pin "7") (pinfunction "7_7") (pintype "passive"))
    )
    (net (code "108") (name "Net-(JP25-Pad8)") (class "Default")
      (node (ref "JP25") (pin "8") (pinfunction "8_8") (pintype "bidirectional"))
      (node (ref "JP26") (pin "6") (pinfunction "6_6") (pintype "passive"))
    )
    (net (code "109") (name "Net-(JP27-Pad1)") (class "Default")
      (node (ref "JP27") (pin "1") (pinfunction "1_1") (pintype "passive"))
      (node (ref "JP27") (pin "2") (pinfunction "2_2") (pintype "passive"))
      (node (ref "JP27") (pin "3") (pinfunction "3_3") (pintype "passive"))
      (node (ref "JP27") (pin "4") (pinfunction "4_4") (pintype "passive"))
      (node (ref "JP27") (pin "5") (pinfunction "5_5") (pintype "passive"))
      (node (ref "JP27") (pin "6") (pinfunction "6_6") (pintype "passive"))
    )
    (net (code "110") (name "Net-(JP28-Pad1)") (class "Default")
      (node (ref "JP28") (pin "1") (pinfunction "1_1") (pintype "passive"))
      (node (ref "JP28") (pin "2") (pinfunction "2_2") (pintype "passive"))
      (node (ref "JP28") (pin "3") (pinfunction "3_3") (pintype "passive"))
      (node (ref "JP28") (pin "4") (pinfunction "4_4") (pintype "passive"))
      (node (ref "JP28") (pin "5") (pinfunction "5_5") (pintype "passive"))
      (node (ref "JP28") (pin "6") (pinfunction "6_6") (pintype "passive"))
    )
    (net (code "111") (name "Net-(JP29-Pad1)") (class "Default")
      (node (ref "JP29") (pin "1") (pinfunction "1_1") (pintype "passive"))
      (node (ref "JP29") (pin "2") (pinfunction "2_2") (pintype "passive"))
      (node (ref "JP29") (pin "3") (pinfunction "3_3") (pintype "passive"))
      (node (ref "JP29") (pin "4") (pinfunction "4_4") (pintype "passive"))
      (node (ref "JP29") (pin "5") (pinfunction "5_5") (pintype "passive"))
      (node (ref "JP29") (pin "6") (pinfunction "6_6") (pintype "passive"))
    )
    (net (code "112") (name "Net-(JP30-Pad1)") (class "Default")
      (node (ref "JP30") (pin "1") (pinfunction "1_1") (pintype "passive"))
      (node (ref "JP30") (pin "2") (pinfunction "2_2") (pintype "passive"))
      (node (ref "JP30") (pin "3") (pinfunction "3_3") (pintype "passive"))
      (node (ref "JP30") (pin "4") (pinfunction "4_4") (pintype "passive"))
      (node (ref "JP30") (pin "5") (pinfunction "5_5") (pintype "passive"))
      (node (ref "JP30") (pin "6") (pinfunction "6_6") (pintype "passive"))
    )
    (net (code "113") (name "Net-(JP31-Pad1)") (class "Default")
      (node (ref "JP31") (pin "1") (pinfunction "1_1") (pintype "passive"))
      (node (ref "JP31") (pin "2") (pinfunction "2_2") (pintype "passive"))
      (node (ref "JP31") (pin "3") (pinfunction "3_3") (pintype "passive"))
      (node (ref "JP31") (pin "4") (pinfunction "4_4") (pintype "passive"))
      (node (ref "JP31") (pin "5") (pinfunction "5_5") (pintype "passive"))
      (node (ref "JP31") (pin "6") (pinfunction "6_6") (pintype "passive"))
    )
    (net (code "114") (name "Net-(JP32-Pad1)") (class "Default")
      (node (ref "JP32") (pin "1") (pinfunction "1_1") (pintype "passive"))
      (node (ref "JP32") (pin "2") (pinfunction "2_2") (pintype "passive"))
      (node (ref "JP32") (pin "3") (pinfunction "3_3") (pintype "passive"))
      (node (ref "JP32") (pin "4") (pinfunction "4_4") (pintype "passive"))
      (node (ref "JP32") (pin "5") (pinfunction "5_5") (pintype "passive"))
      (node (ref "JP32") (pin "6") (pinfunction "6_6") (pintype "passive"))
    )
    (net (code "115") (name "Net-(JP33-Pad1)") (class "Default")
      (node (ref "JP33") (pin "1") (pinfunction "1_1") (pintype "passive"))
      (node (ref "JP33") (pin "2") (pinfunction "2_2") (pintype "passive"))
      (node (ref "JP33") (pin "3") (pinfunction "3_3") (pintype "passive"))
      (node (ref "JP33") (pin "4") (pinfunction "4_4") (pintype "passive"))
      (node (ref "JP33") (pin "5") (pinfunction "5_5") (pintype "passive"))
      (node (ref "JP33") (pin "6") (pinfunction "6_6") (pintype "passive"))
    )
    (net (code "116") (name "Net-(JP34-Pad1)") (class "Default")
      (node (ref "JP34") (pin "1") (pinfunction "1_1") (pintype "passive"))
      (node (ref "JP34") (pin "2") (pinfunction "2_2") (pintype "passive"))
      (node (ref "JP34") (pin "3") (pinfunction "3_3") (pintype "passive"))
      (node (ref "JP34") (pin "4") (pinfunction "4_4") (pintype "passive"))
      (node (ref "JP34") (pin "5") (pinfunction "5_5") (pintype "passive"))
      (node (ref "JP34") (pin "6") (pinfunction "6_6") (pintype "passive"))
    )
    (net (code "117") (name "Net-(JP35-Pad1)") (class "Default")
      (node (ref "JP35") (pin "1") (pinfunction "1_1") (pintype "passive"))
      (node (ref "JP35") (pin "2") (pinfunction "2_2") (pintype "passive"))
      (node (ref "JP35") (pin "3") (pinfunction "3_3") (pintype "passive"))
      (node (ref "JP35") (pin "4") (pinfunction "4_4") (pintype "passive"))
      (node (ref "JP35") (pin "5") (pinfunction "5_5") (pintype "passive"))
      (node (ref "JP35") (pin "6") (pinfunction "6_6") (pintype "passive"))
    )
    (net (code "118") (name "Net-(JP36-Pad1)") (class "Default")
      (node (ref "JP36") (pin "1") (pinfunction "1_1") (pintype "passive"))
      (node (ref "JP36") (pin "2") (pinfunction "2_2") (pintype "passive"))
      (node (ref "JP36") (pin "3") (pinfunction "3_3") (pintype "passive"))
      (node (ref "JP36") (pin "4") (pinfunction "4_4") (pintype "passive"))
      (node (ref "JP36") (pin "5") (pinfunction "5_5") (pintype "passive"))
      (node (ref "JP36") (pin "6") (pinfunction "6_6") (pintype "passive"))
    )
    (net (code "119") (name "Net-(JP37-Pad1)") (class "Default")
      (node (ref "JP37") (pin "1") (pinfunction "1_1") (pintype "passive"))
      (node (ref "JP37") (pin "2") (pinfunction "2_2") (pintype "passive"))
      (node (ref "JP37") (pin "3") (pinfunction "3_3") (pintype "passive"))
      (node (ref "JP37") (pin "4") (pinfunction "4_4") (pintype "passive"))
      (node (ref "JP37") (pin "5") (pinfunction "5_5") (pintype "passive"))
      (node (ref "JP37") (pin "6") (pinfunction "6_6") (pintype "passive"))
    )
    (net (code "120") (name "Net-(JP38-Pad1)") (class "Default")
      (node (ref "JP38") (pin "1") (pinfunction "1_1") (pintype "passive"))
      (node (ref "JP38") (pin "2") (pinfunction "2_2") (pintype "passive"))
      (node (ref "JP38") (pin "3") (pinfunction "3_3") (pintype "passive"))
      (node (ref "JP38") (pin "4") (pinfunction "4_4") (pintype "passive"))
      (node (ref "JP38") (pin "5") (pinfunction "5_5") (pintype "passive"))
      (node (ref "JP38") (pin "6") (pinfunction "6_6") (pintype "passive"))
    )
  )
)
